# 2_-MCU.net
KiCad netlist of a schematic drawn in Altium Designer
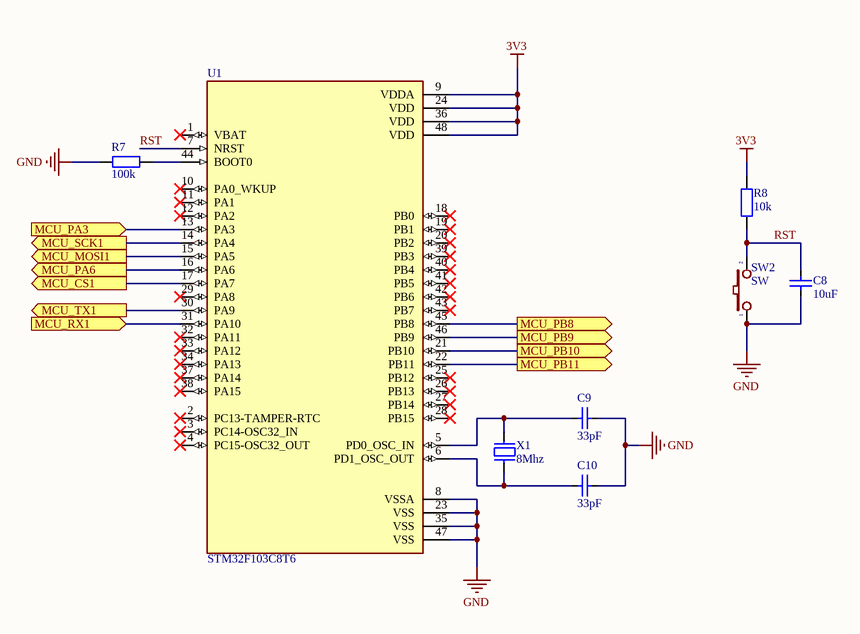
[diagram p0: [2]-MCU.SchDoc]

(export (version "E")
  (design (tool "Eeschema 10.0.6"))
  (components
    (comp (ref "C8")
      (value "10uF")
      (footprint "CAP_0805")
      (description "Capacitor")
      (fields (field (name "PUBLISHER") "Altium Limited"))
      (libsource (lib "My Library") (part "CapSMD"))
    )
    (comp (ref "C9")
      (value "33pF")
      (footprint "CAP_0805")
      (description "Capacitor")
      (fields (field (name "PUBLISHER") "Altium Limited"))
      (libsource (lib "My Library") (part "CapSMD"))
    )
    (comp (ref "C10")
      (value "33pF")
      (footprint "CAP_0805")
      (description "Capacitor")
      (fields (field (name "PUBLISHER") "Altium Limited"))
      (libsource (lib "My Library") (part "CapSMD"))
    )
    (comp (ref "R7")
      (value "100k")
      (footprint "RES-SMD-0805")
      (description "Resistor SMD")
      (fields
        (field (name "MANUFACTURER") "Generic Components")
        (field (name "PUBLISHER") "Altium Hobart Technology Centre")
      )
      (libsource (lib "My Library") (part "Resistor - SMD"))
    )
    (comp (ref "R8")
      (value "10k")
      (footprint "RES-SMD-0805")
      (description "Resistor SMD")
      (fields
        (field (name "MANUFACTURER") "Generic Components")
        (field (name "PUBLISHER") "Altium Hobart Technology Centre")
      )
      (libsource (lib "My Library") (part "Resistor - SMD"))
    )
    (comp (ref "SW2")
      (value "SW")
      (footprint "SW-SMD")
      (description "Switch button 2 pin")
      (libsource (lib "My Library") (part "SW2"))
    )
    (comp (ref "U1")
      (value "STM32F103C8T6")
      (footprint "QFP50P900X900X160-48N")
      (description "ARMÂ® CortexÂ®-M3 STM32F1 Microcontroller IC 32-Bit 72MHz 64KB (64K x 8) FLASH 48-LQFP (7x7)")
      (fields (field (name "MF") "STMicroelectronics"))
      (libsource (lib "STM32F103C8T6") (part "STM32F103C8T6"))
    )
    (comp (ref "X1")
      (value "8Mhz")
      (footprint "X2-SMD-5.0X3.2X1.3MM")
      (description "Crystal For all Crystal 2pin.")
      (libsource (lib "My Library") (part "XT2"))
    )
  )
  (nets
    (net (code "1") (name "/MCU_CS1") (class "Default")
      (node (ref "U1") (pin "17") (pinfunction "PA7_17") (pintype "bidirectional"))
    )
    (net (code "2") (name "/MCU_MOSI1") (class "Default")
      (node (ref "U1") (pin "15") (pinfunction "PA5_15") (pintype "bidirectional"))
    )
    (net (code "3") (name "/MCU_PA3") (class "Default")
      (node (ref "U1") (pin "13") (pinfunction "PA3_13") (pintype "bidirectional"))
    )
    (net (code "4") (name "/MCU_PA6") (class "Default")
      (node (ref "U1") (pin "16") (pinfunction "PA6_16") (pintype "bidirectional"))
    )
    (net (code "5") (name "/MCU_PB8") (class "Default")
      (node (ref "U1") (pin "45") (pinfunction "PB8_45") (pintype "bidirectional"))
    )
    (net (code "6") (name "/MCU_PB9") (class "Default")
      (node (ref "U1") (pin "46") (pinfunction "PB9_46") (pintype "bidirectional"))
    )
    (net (code "7") (name "/MCU_PB10") (class "Default")
      (node (ref "U1") (pin "21") (pinfunction "PB10_21") (pintype "bidirectional"))
    )
    (net (code "8") (name "/MCU_PB11") (class "Default")
      (node (ref "U1") (pin "22") (pinfunction "PB11_22") (pintype "bidirectional"))
    )
    (net (code "9") (name "/MCU_RX1") (class "Default")
      (node (ref "U1") (pin "31") (pinfunction "PA10_31") (pintype "bidirectional"))
    )
    (net (code "10") (name "/MCU_SCK1") (class "Default")
      (node (ref "U1") (pin "14") (pinfunction "PA4_14") (pintype "bidirectional"))
    )
    (net (code "11") (name "/MCU_TX1") (class "Default")
      (node (ref "U1") (pin "30") (pinfunction "PA9_30") (pintype "bidirectional"))
    )
    (net (code "12") (name "/RST") (class "Default")
      (node (ref "C8") (pin "2") (pinfunction "2_2") (pintype "passive"))
      (node (ref "R8") (pin "2") (pinfunction "2_2") (pintype "passive"))
      (node (ref "SW2") (pin "2") (pinfunction "2_2") (pintype "passive"))
      (node (ref "U1") (pin "7") (pinfunction "NRST_7") (pintype "input"))
    )
    (net (code "13") (name "3V3") (class "Default")
      (node (ref "R8") (pin "1") (pinfunction "1_1") (pintype "passive"))
      (node (ref "U1") (pin "24") (pinfunction "VDD_24") (pintype "power_in"))
      (node (ref "U1") (pin "36") (pinfunction "VDD_36") (pintype "power_in"))
      (node (ref "U1") (pin "48") (pinfunction "VDD_48") (pintype "power_in"))
      (node (ref "U1") (pin "9") (pinfunction "VDDA_9") (pintype "power_in"))
    )
    (net (code "14") (name "GND") (class "Default")
      (node (ref "C10") (pin "2") (pinfunction "2_2") (pintype "passive"))
      (node (ref "C8") (pin "1") (pinfunction "1_1") (pintype "passive"))
      (node (ref "C9") (pin "2") (pinfunction "2_2") (pintype "passive"))
      (node (ref "R7") (pin "1") (pinfunction "1_1") (pintype "passive"))
      (node (ref "SW2") (pin "1") (pinfunction "1_1") (pintype "passive"))
      (node (ref "U1") (pin "23") (pinfunction "VSS_23") (pintype "power_in"))
      (node (ref "U1") (pin "35") (pinfunction "VSS_35") (pintype "power_in"))
      (node (ref "U1") (pin "47") (pinfunction "VSS_47") (pintype "power_in"))
      (node (ref "U1") (pin "8") (pinfunction "VSSA_8") (pintype "power_in"))
    )
    (net (code "15") (name "Net-(U1-BOOT0)") (class "Default")
      (node (ref "R7") (pin "2") (pinfunction "2_2") (pintype "passive"))
      (node (ref "U1") (pin "44") (pinfunction "BOOT0_44") (pintype "input"))
    )
    (net (code "16") (name "Net-(U1-PD0_OSC_IN)") (class "Default")
      (node (ref "C9") (pin "1") (pinfunction "1_1") (pintype "passive"))
      (node (ref "U1") (pin "5") (pinfunction "PD0_OSC_IN_5") (pintype "bidirectional"))
      (node (ref "X1") (pin "2") (pinfunction "2_2") (pintype "passive"))
    )
    (net (code "17") (name "Net-(U1-PD1_OSC_OUT)") (class "Default")
      (node (ref "C10") (pin "1") (pinfunction "1_1") (pintype "passive"))
      (node (ref "U1") (pin "6") (pinfunction "PD1_OSC_OUT_6") (pintype "bidirectional"))
      (node (ref "X1") (pin "1") (pinfunction "1_1") (pintype "passive"))
    )
    (net (code "18") (name "unconnected-(U1-PA0_WKUP-Pad10)") (class "Default")
      (node (ref "U1") (pin "10") (pinfunction "PA0_WKUP_10") (pintype "bidirectional+no_connect"))
    )
    (net (code "19") (name "unconnected-(U1-PA1-Pad11)") (class "Default")
      (node (ref "U1") (pin "11") (pinfunction "PA1_11") (pintype "bidirectional+no_connect"))
    )
    (net (code "20") (name "unconnected-(U1-PA2-Pad12)") (class "Default")
      (node (ref "U1") (pin "12") (pinfunction "PA2_12") (pintype "bidirectional+no_connect"))
    )
    (net (code "21") (name "unconnected-(U1-PA8-Pad29)") (class "Default")
      (node (ref "U1") (pin "29") (pinfunction "PA8_29") (pintype "bidirectional+no_connect"))
    )
    (net (code "22") (name "unconnected-(U1-PA11-Pad32)") (class "Default")
      (node (ref "U1") (pin "32") (pinfunction "PA11_32") (pintype "bidirectional+no_connect"))
    )
    (net (code "23") (name "unconnected-(U1-PA12-Pad33)") (class "Default")
      (node (ref "U1") (pin "33") (pinfunction "PA12_33") (pintype "bidirectional+no_connect"))
    )
    (net (code "24") (name "unconnected-(U1-PA13-Pad34)") (class "Default")
      (node (ref "U1") (pin "34") (pinfunction "PA13_34") (pintype "bidirectional+no_connect"))
    )
    (net (code "25") (name "unconnected-(U1-PA14-Pad37)") (class "Default")
      (node (ref "U1") (pin "37") (pinfunction "PA14_37") (pintype "bidirectional+no_connect"))
    )
    (net (code "26") (name "unconnected-(U1-PA15-Pad38)") (class "Default")
      (node (ref "U1") (pin "38") (pinfunction "PA15_38") (pintype "bidirectional+no_connect"))
    )
    (net (code "27") (name "unconnected-(U1-PB0-Pad18)") (class "Default")
      (node (ref "U1") (pin "18") (pinfunction "PB0_18") (pintype "bidirectional+no_connect"))
    )
    (net (code "28") (name "unconnected-(U1-PB1-Pad19)") (class "Default")
      (node (ref "U1") (pin "19") (pinfunction "PB1_19") (pintype "bidirectional+no_connect"))
    )
    (net (code "29") (name "unconnected-(U1-PB2-Pad20)") (class "Default")
      (node (ref "U1") (pin "20") (pinfunction "PB2_20") (pintype "bidirectional+no_connect"))
    )
    (net (code "30") (name "unconnected-(U1-PB3-Pad39)") (class "Default")
      (node (ref "U1") (pin "39") (pinfunction "PB3_39") (pintype "bidirectional+no_connect"))
    )
    (net (code "31") (name "unconnected-(U1-PB4-Pad40)") (class "Default")
      (node (ref "U1") (pin "40") (pinfunction "PB4_40") (pintype "bidirectional+no_connect"))
    )
    (net (code "32") (name "unconnected-(U1-PB5-Pad41)") (class "Default")
      (node (ref "U1") (pin "41") (pinfunction "PB5_41") (pintype "bidirectional+no_connect"))
    )
    (net (code "33") (name "unconnected-(U1-PB6-Pad42)") (class "Default")
      (node (ref "U1") (pin "42") (pinfunction "PB6_42") (pintype "bidirectional+no_connect"))
    )
    (net (code "34") (name "unconnected-(U1-PB7-Pad43)") (class "Default")
      (node (ref "U1") (pin "43") (pinfunction "PB7_43") (pintype "bidirectional+no_connect"))
    )
    (net (code "35") (name "unconnected-(U1-PB12-Pad25)") (class "Default")
      (node (ref "U1") (pin "25") (pinfunction "PB12_25") (pintype "bidirectional+no_connect"))
    )
    (net (code "36") (name "unconnected-(U1-PB13-Pad26)") (class "Default")
      (node (ref "U1") (pin "26") (pinfunction "PB13_26") (pintype "bidirectional+no_connect"))
    )
    (net (code "37") (name "unconnected-(U1-PB14-Pad27)") (class "Default")
      (node (ref "U1") (pin "27") (pinfunction "PB14_27") (pintype "bidirectional+no_connect"))
    )
    (net (code "38") (name "unconnected-(U1-PB15-Pad28)") (class "Default")
      (node (ref "U1") (pin "28") (pinfunction "PB15_28") (pintype "bidirectional+no_connect"))
    )
    (net (code "39") (name "unconnected-(U1-PC13-TAMPER-RTC-Pad2)") (class "Default")
      (node (ref "U1") (pin "2") (pinfunction "PC13-TAMPER-RTC_2") (pintype "bidirectional+no_connect"))
    )
    (net (code "40") (name "unconnected-(U1-PC14-OSC32_IN-Pad3)") (class "Default")
      (node (ref "U1") (pin "3") (pinfunction "PC14-OSC32_IN_3") (pintype "bidirectional+no_connect"))
    )
    (net (code "41") (name "unconnected-(U1-PC15-OSC32_OUT-Pad4)") (class "Default")
      (node (ref "U1") (pin "4") (pinfunction "PC15-OSC32_OUT_4") (pintype "bidirectional+no_connect"))
    )
    (net (code "42") (name "unconnected-(U1-VBAT-Pad1)") (class "Default")
      (node (ref "U1") (pin "1") (pinfunction "VBAT_1") (pintype "bidirectional+no_connect"))
    )
  )
)
